# Min_Sys.net
KiCad netlist of a schematic drawn in Altium Designer
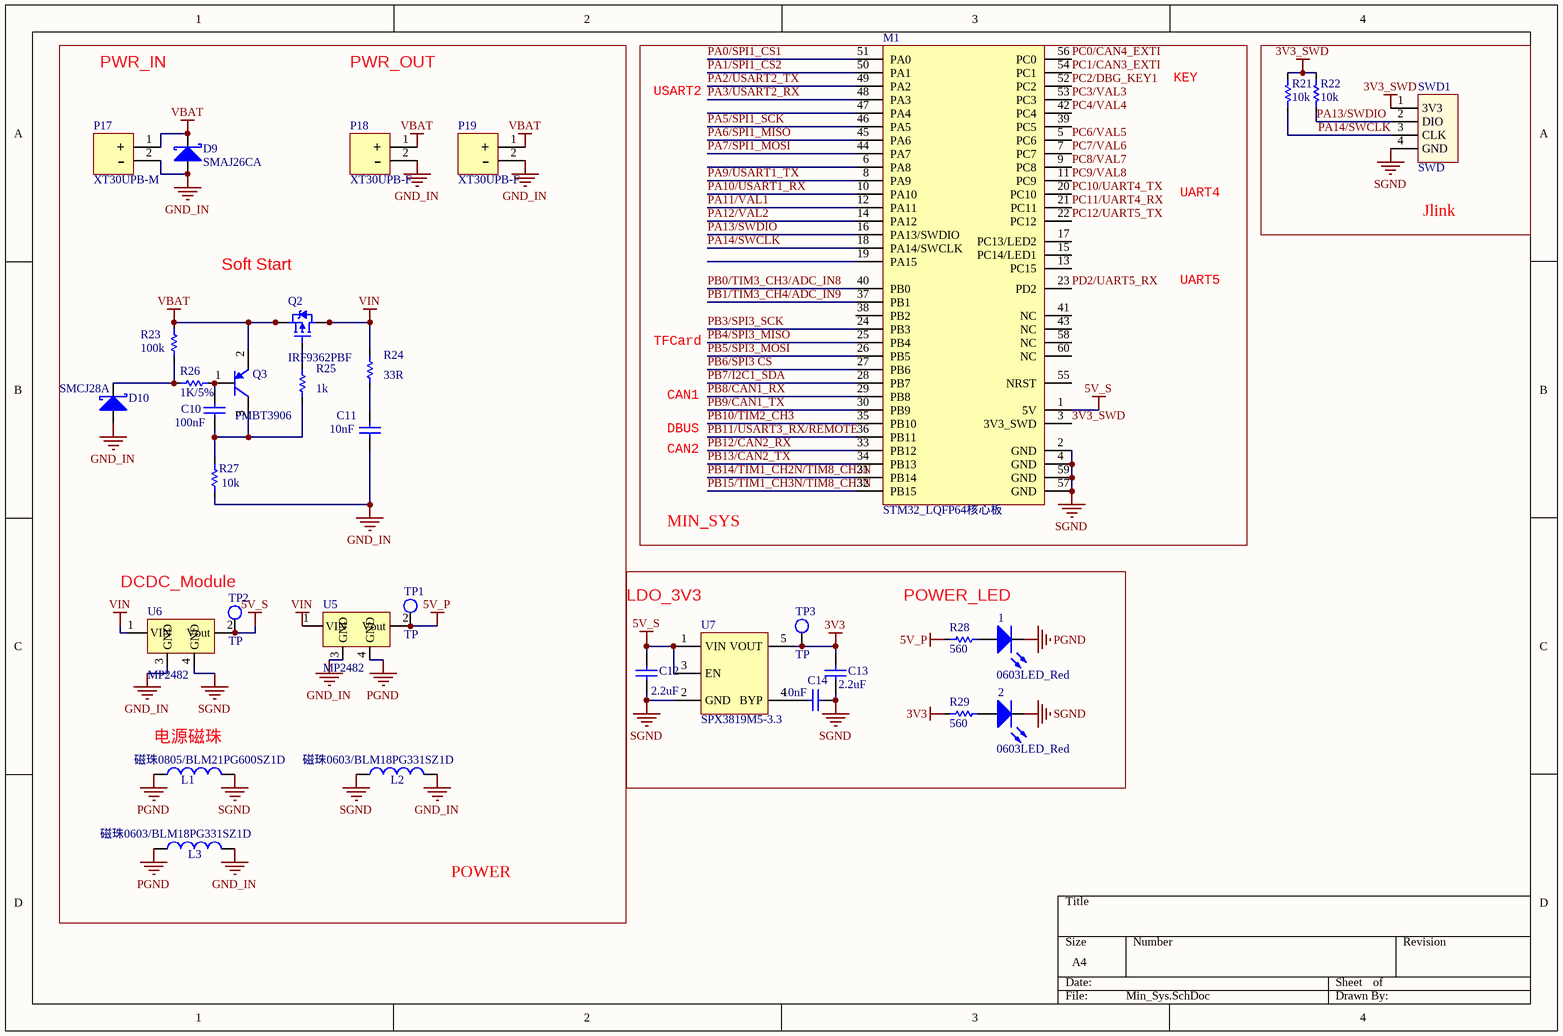
[diagram p0: Min_Sys.SchDoc]

(export (version "E")
  (design (tool "Eeschema 10.0.6"))
  (components
    (comp (ref "1")
      (value "0603LED_Red")
      (footprint "0603LED_R")
      (description "Typical RED, GREEN, YELLOW, AMBER GaAs LED")
      (fields (field (name "PUBLISHER") "Altium Limited"))
      (libsource (lib "MyComponents_v2.5") (part "LED"))
    )
    (comp (ref "2")
      (value "0603LED_Red")
      (footprint "0603LED_R")
      (description "Typical RED, GREEN, YELLOW, AMBER GaAs LED")
      (fields (field (name "PUBLISHER") "Altium Limited"))
      (libsource (lib "MyComponents_v2.5") (part "LED"))
    )
    (comp (ref "C10")
      (value "100nF")
      (footprint "0603C")
      (description "Capacitor")
      (fields (field (name "PUBLISHER") "Altium Limited"))
      (libsource (lib "") (part "Cap_1"))
    )
    (comp (ref "C11")
      (value "10nF")
      (footprint "0603C")
      (description "Capacitor")
      (fields (field (name "PUBLISHER") "Altium Limited"))
      (libsource (lib "") (part "Cap_1"))
    )
    (comp (ref "C12")
      (value "2.2uF")
      (footprint "0603C")
      (description "Capacitor")
      (fields (field (name "PUBLISHER") "Altium Limited"))
      (libsource (lib "MyComponents_v2.5") (part "Cap"))
    )
    (comp (ref "C13")
      (value "2.2uF")
      (footprint "0603C")
      (description "Capacitor")
      (fields (field (name "PUBLISHER") "Altium Limited"))
      (libsource (lib "MyComponents_v2.5") (part "Cap"))
    )
    (comp (ref "C14")
      (value "10nF")
      (footprint "0603C")
      (description "Capacitor")
      (fields (field (name "PUBLISHER") "Altium Limited"))
      (libsource (lib "MyComponents_v2.5") (part "Cap"))
    )
    (comp (ref "D9")
      (value "SMAJ26CA")
      (footprint "SMA/DO-214AC")
      (description "Schottky Diode")
      (fields (field (name "PUBLISHER") "Altium Limited"))
      (libsource (lib "MyComponents_v2.5") (part "D Schottky_SMAF"))
    )
    (comp (ref "D10")
      (value "SMCJ28A")
      (footprint "SMA/DO-214AC")
      (description "Schottky Diode")
      (fields (field (name "PUBLISHER") "Altium Limited"))
      (libsource (lib "MyComponents_v2.5") (part "D Schottky_SMAF"))
    )
    (comp (ref "L1")
      (value "磁珠0805/BLM21PG600SZ1D")
      (footprint "0805L")
      (description "Inductor")
      (fields (field (name "PUBLISHER") "Altium Limited"))
      (libsource (lib "MyComponents_v2.5") (part "Inductor"))
    )
    (comp (ref "L2")
      (value "磁珠0603/BLM18PG331SZ1D")
      (footprint "0603L")
      (description "Inductor")
      (fields (field (name "PUBLISHER") "Altium Limited"))
      (libsource (lib "MyComponents_v2.5") (part "Inductor"))
    )
    (comp (ref "L3")
      (value "磁珠0603/BLM18PG331SZ1D")
      (footprint "0603L")
      (description "Inductor")
      (fields (field (name "PUBLISHER") "Altium Limited"))
      (libsource (lib "MyComponents_v2.5") (part "Inductor"))
    )
    (comp (ref "M1")
      (value "STM32_LQFP64核心板")
      (footprint "STM32_LQFP64核心板")
      (description "STM32_LQFP64核心板\r\n兼容F105Rx、F405RGT6、F446Rx\r\n尺寸23mm x 25mm")
      (libsource (lib "MyComponents_v2.5") (part "STM32_LQFP64核心板"))
    )
    (comp (ref "P17")
      (value "XT30UPB-M")
      (footprint "XT30UPB-MALE")
      (libsource (lib "MyComponents_v2.5") (part "XT30/60/90"))
    )
    (comp (ref "P18")
      (value "XT30UPB-F")
      (footprint "XT30UPB-FEMALE")
      (libsource (lib "MyComponents_v2.5") (part "XT30/60/90"))
    )
    (comp (ref "P19")
      (value "XT30UPB-F")
      (footprint "XT30UPB-FEMALE")
      (libsource (lib "MyComponents_v2.5") (part "XT30/60/90"))
    )
    (comp (ref "Q2")
      (value "IRF9362PBF")
      (footprint "SON5X6")
      (description "P-Channel Power MOSFET")
      (fields (field (name "PUBLISHER") "Altium Limited"))
      (libsource (lib "MyComponents_v2.5") (part "PMOS"))
    )
    (comp (ref "Q3")
      (value "PMBT3906")
      (footprint "SOT-23-3")
      (description "PNP Bipolar Transistor")
      (fields (field (name "PUBLISHER") "Altium Limited"))
      (libsource (lib "MyComponents_v2.5") (part "PNP"))
    )
    (comp (ref "R21")
      (value "10k")
      (footprint "0603R")
      (description "Resistor")
      (fields (field (name "PUBLISHER") "Altium Limited"))
      (libsource (lib "") (part "Res1_1"))
    )
    (comp (ref "R22")
      (value "10k")
      (footprint "0603R")
      (description "Resistor")
      (fields (field (name "PUBLISHER") "Altium Limited"))
      (libsource (lib "") (part "Res1_1"))
    )
    (comp (ref "R23")
      (value "100k")
      (footprint "0603R")
      (description "Resistor")
      (fields (field (name "PUBLISHER") "Altium Limited"))
      (libsource (lib "MyComponents_v2.5") (part "Res1"))
    )
    (comp (ref "R24")
      (value "33R")
      (footprint "0603R")
      (description "Resistor")
      (fields (field (name "PUBLISHER") "Altium Limited"))
      (libsource (lib "MyComponents_v2.5") (part "Res1"))
    )
    (comp (ref "R25")
      (value "1k")
      (footprint "0603R")
      (description "Resistor")
      (fields (field (name "PUBLISHER") "Altium Limited"))
      (libsource (lib "MyComponents_v2.5") (part "Res1"))
    )
    (comp (ref "R26")
      (value "1K/5%")
      (footprint "0603R")
      (description "Resistor")
      (fields (field (name "PUBLISHER") "Altium Limited"))
      (libsource (lib "MyComponents_v2.5") (part "Res1"))
    )
    (comp (ref "R27")
      (value "10k")
      (footprint "0603R")
      (description "Resistor")
      (fields (field (name "PUBLISHER") "Altium Limited"))
      (libsource (lib "MyComponents_v2.5") (part "Res1"))
    )
    (comp (ref "R28")
      (value "560")
      (footprint "0603R")
      (description "Resistor")
      (fields (field (name "PUBLISHER") "Altium Limited"))
      (libsource (lib "") (part "Res1_1"))
    )
    (comp (ref "R29")
      (value "560")
      (footprint "0603R")
      (description "Resistor")
      (fields (field (name "PUBLISHER") "Altium Limited"))
      (libsource (lib "") (part "Res1_1"))
    )
    (comp (ref "SWD1")
      (value "SWD")
      (footprint "HEADER 4x1")
      (libsource (lib "MyComponents_v2.5") (part "SWD_HEADER"))
    )
    (comp (ref "TP1")
      (value "TP")
      (footprint "TP_VIA")
      (description "Test Point")
      (libsource (lib "MyComponents_v2.5") (part "TP"))
    )
    (comp (ref "TP2")
      (value "TP")
      (footprint "TP_VIA")
      (description "Test Point")
      (libsource (lib "MyComponents_v2.5") (part "TP"))
    )
    (comp (ref "TP3")
      (value "TP")
      (footprint "TP_VIA")
      (description "Test Point")
      (libsource (lib "MyComponents_v2.5") (part "TP"))
    )
    (comp (ref "U5")
      (value "MP2482")
      (footprint "MP2482_PowerModule")
      (libsource (lib "MyComponents_v2.5") (part "MP2482_PowerModule"))
    )
    (comp (ref "U6")
      (value "MP2482")
      (footprint "MP2482_PowerModule")
      (libsource (lib "MyComponents_v2.5") (part "MP2482_PowerModule"))
    )
    (comp (ref "U7")
      (value "SPX3819M5-3.3")
      (footprint "SOT-23-5 L")
      (libsource (lib "MyComponents_v2.5") (part "LDO_SOT23-5"))
    )
  )
  (nets
    (net (code "1") (name "/PA0{slash}SPI1_CS1") (class "Default")
      (node (ref "M1") (pin "51") (pinfunction "PA0_51") (pintype "passive"))
    )
    (net (code "2") (name "/PA1{slash}SPI1_CS2") (class "Default")
      (node (ref "M1") (pin "50") (pinfunction "PA1_50") (pintype "passive"))
    )
    (net (code "3") (name "/PA2{slash}USART2_TX") (class "Default")
      (node (ref "M1") (pin "49") (pinfunction "PA2_49") (pintype "passive"))
    )
    (net (code "4") (name "/PA3{slash}USART2_RX") (class "Default")
      (node (ref "M1") (pin "48") (pinfunction "PA3_48") (pintype "passive"))
    )
    (net (code "5") (name "/PA5{slash}SPI1_SCK") (class "Default")
      (node (ref "M1") (pin "46") (pinfunction "PA5_46") (pintype "passive"))
    )
    (net (code "6") (name "/PA6{slash}SPI1_MISO") (class "Default")
      (node (ref "M1") (pin "45") (pinfunction "PA6_45") (pintype "passive"))
    )
    (net (code "7") (name "/PA7{slash}SPI1_MOSI") (class "Default")
      (node (ref "M1") (pin "44") (pinfunction "PA7_44") (pintype "passive"))
    )
    (net (code "8") (name "/PA9{slash}USART1_TX") (class "Default")
      (node (ref "M1") (pin "8") (pinfunction "PA9_8") (pintype "passive"))
    )
    (net (code "9") (name "/PA10{slash}USART1_RX") (class "Default")
      (node (ref "M1") (pin "10") (pinfunction "PA10_10") (pintype "passive"))
    )
    (net (code "10") (name "/PA11{slash}VAL1") (class "Default")
      (node (ref "M1") (pin "12") (pinfunction "PA11_12") (pintype "passive"))
    )
    (net (code "11") (name "/PA12{slash}VAL2") (class "Default")
      (node (ref "M1") (pin "14") (pinfunction "PA12_14") (pintype "passive"))
    )
    (net (code "12") (name "/PA13{slash}SWDIO") (class "Default")
      (node (ref "M1") (pin "16") (pinfunction "PA13/SWDIO_16") (pintype "passive"))
      (node (ref "R22") (pin "1") (pinfunction "1_1") (pintype "passive"))
      (node (ref "SWD1") (pin "2") (pinfunction "DIO_2") (pintype "passive"))
    )
    (net (code "13") (name "/PA14{slash}SWCLK") (class "Default")
      (node (ref "M1") (pin "18") (pinfunction "PA14/SWCLK_18") (pintype "passive"))
      (node (ref "R21") (pin "1") (pinfunction "1_1") (pintype "passive"))
      (node (ref "SWD1") (pin "3") (pinfunction "CLK_3") (pintype "passive"))
    )
    (net (code "14") (name "/PB0{slash}TIM3_CH3{slash}ADC_IN8") (class "Default")
      (node (ref "M1") (pin "40") (pinfunction "PB0_40") (pintype "passive"))
    )
    (net (code "15") (name "/PB1{slash}TIM3_CH4{slash}ADC_IN9") (class "Default")
      (node (ref "M1") (pin "37") (pinfunction "PB1_37") (pintype "passive"))
    )
    (net (code "16") (name "/PB3{slash}SPI3_SCK") (class "Default")
      (node (ref "M1") (pin "24") (pinfunction "PB3_24") (pintype "passive"))
    )
    (net (code "17") (name "/PB4{slash}SPI3_MISO") (class "Default")
      (node (ref "M1") (pin "25") (pinfunction "PB4_25") (pintype "passive"))
    )
    (net (code "18") (name "/PB5{slash}SPI3_MOSI") (class "Default")
      (node (ref "M1") (pin "26") (pinfunction "PB5_26") (pintype "passive"))
    )
    (net (code "19") (name "/PB6{slash}SPI3 CS") (class "Default")
      (node (ref "M1") (pin "27") (pinfunction "PB6_27") (pintype "passive"))
    )
    (net (code "20") (name "/PB7{slash}I2C1_SDA") (class "Default")
      (node (ref "M1") (pin "28") (pinfunction "PB7_28") (pintype "passive"))
    )
    (net (code "21") (name "/PB8{slash}CAN1_RX") (class "Default")
      (node (ref "M1") (pin "29") (pinfunction "PB8_29") (pintype "passive"))
    )
    (net (code "22") (name "/PB9{slash}CAN1_TX") (class "Default")
      (node (ref "M1") (pin "30") (pinfunction "PB9_30") (pintype "passive"))
    )
    (net (code "23") (name "/PB10{slash}TIM2_CH3") (class "Default")
      (node (ref "M1") (pin "35") (pinfunction "PB10_35") (pintype "passive"))
    )
    (net (code "24") (name "/PB11{slash}USART3_RX{slash}REMOTE") (class "Default")
      (node (ref "M1") (pin "36") (pinfunction "PB11_36") (pintype "passive"))
    )
    (net (code "25") (name "/PB12{slash}CAN2_RX") (class "Default")
      (node (ref "M1") (pin "33") (pinfunction "PB12_33") (pintype "passive"))
    )
    (net (code "26") (name "/PB13{slash}CAN2_TX") (class "Default")
      (node (ref "M1") (pin "34") (pinfunction "PB13_34") (pintype "passive"))
    )
    (net (code "27") (name "/PB14{slash}TIM1_CH2N{slash}TIM8_CH2N") (class "Default")
      (node (ref "M1") (pin "31") (pinfunction "PB14_31") (pintype "passive"))
    )
    (net (code "28") (name "/PB15{slash}TIM1_CH3N{slash}TIM8_CH3N") (class "Default")
      (node (ref "M1") (pin "32") (pinfunction "PB15_32") (pintype "passive"))
    )
    (net (code "29") (name "/PC0{slash}CAN4_EXTI") (class "Default")
      (node (ref "M1") (pin "56") (pinfunction "PC0_56") (pintype "passive"))
    )
    (net (code "30") (name "/PC1{slash}CAN3_EXTI") (class "Default")
      (node (ref "M1") (pin "54") (pinfunction "PC1_54") (pintype "passive"))
    )
    (net (code "31") (name "/PC2{slash}DBG_KEY1") (class "Default")
      (node (ref "M1") (pin "52") (pinfunction "PC2_52") (pintype "passive"))
    )
    (net (code "32") (name "/PC3{slash}VAL3") (class "Default")
      (node (ref "M1") (pin "53") (pinfunction "PC3_53") (pintype "passive"))
    )
    (net (code "33") (name "/PC4{slash}VAL4") (class "Default")
      (node (ref "M1") (pin "42") (pinfunction "PC4_42") (pintype "passive"))
    )
    (net (code "34") (name "/PC6{slash}VAL5") (class "Default")
      (node (ref "M1") (pin "5") (pinfunction "PC6_5") (pintype "passive"))
    )
    (net (code "35") (name "/PC7{slash}VAL6") (class "Default")
      (node (ref "M1") (pin "7") (pinfunction "PC7_7") (pintype "passive"))
    )
    (net (code "36") (name "/PC8{slash}VAL7") (class "Default")
      (node (ref "M1") (pin "9") (pinfunction "PC8_9") (pintype "passive"))
    )
    (net (code "37") (name "/PC9{slash}VAL8") (class "Default")
      (node (ref "M1") (pin "11") (pinfunction "PC9_11") (pintype "passive"))
    )
    (net (code "38") (name "/PC10{slash}UART4_TX") (class "Default")
      (node (ref "M1") (pin "20") (pinfunction "PC10_20") (pintype "passive"))
    )
    (net (code "39") (name "/PC11{slash}UART4_RX") (class "Default")
      (node (ref "M1") (pin "21") (pinfunction "PC11_21") (pintype "passive"))
    )
    (net (code "40") (name "/PC12{slash}UART5_TX") (class "Default")
      (node (ref "M1") (pin "22") (pinfunction "PC12_22") (pintype "passive"))
    )
    (net (code "41") (name "/PD2{slash}UART5_RX") (class "Default")
      (node (ref "M1") (pin "23") (pinfunction "PD2_23") (pintype "passive"))
    )
    (net (code "42") (name "3V3") (class "Default")
      (node (ref "C13") (pin "1") (pinfunction "1_1") (pintype "passive"))
      (node (ref "R29") (pin "2") (pinfunction "2_2") (pintype "passive"))
      (node (ref "TP3") (pin "1") (pinfunction "TP_1") (pintype "open_collector"))
      (node (ref "U7") (pin "5") (pinfunction "VOUT_5") (pintype "passive"))
    )
    (net (code "43") (name "3V3_SWD") (class "Default")
      (node (ref "M1") (pin "3") (pinfunction "3V3_SWD_3") (pintype "passive"))
      (node (ref "R21") (pin "2") (pinfunction "2_2") (pintype "passive"))
      (node (ref "R22") (pin "2") (pinfunction "2_2") (pintype "passive"))
      (node (ref "SWD1") (pin "1") (pinfunction "3V3_1") (pintype "passive"))
    )
    (net (code "44") (name "5V_P") (class "Default")
      (node (ref "R28") (pin "2") (pinfunction "2_2") (pintype "passive"))
      (node (ref "TP1") (pin "1") (pinfunction "TP_1") (pintype "open_collector"))
      (node (ref "U5") (pin "2") (pinfunction "Vout_2") (pintype "passive"))
    )
    (net (code "45") (name "5V_S") (class "Default")
      (node (ref "C12") (pin "2") (pinfunction "2_2") (pintype "passive"))
      (node (ref "M1") (pin "1") (pinfunction "5V_1") (pintype "passive"))
      (node (ref "TP2") (pin "1") (pinfunction "TP_1") (pintype "open_collector"))
      (node (ref "U6") (pin "2") (pinfunction "Vout_2") (pintype "passive"))
      (node (ref "U7") (pin "1") (pinfunction "VIN_1") (pintype "passive"))
      (node (ref "U7") (pin "3") (pinfunction "EN_3") (pintype "passive"))
    )
    (net (code "46") (name "GND_IN") (class "Default")
      (node (ref "C11") (pin "1") (pinfunction "1_1") (pintype "passive"))
      (node (ref "D10") (pin "1") (pinfunction "1_1") (pintype "passive"))
      (node (ref "D9") (pin "1") (pinfunction "1_1") (pintype "passive"))
      (node (ref "L2") (pin "2") (pinfunction "2_2") (pintype "passive"))
      (node (ref "L3") (pin "2") (pinfunction "2_2") (pintype "passive"))
      (node (ref "P17") (pin "2") (pinfunction "-_2") (pintype "passive"))
      (node (ref "P18") (pin "2") (pinfunction "-_2") (pintype "passive"))
      (node (ref "P19") (pin "2") (pinfunction "-_2") (pintype "passive"))
      (node (ref "R27") (pin "2") (pinfunction "2_2") (pintype "passive"))
      (node (ref "U5") (pin "3") (pinfunction "GND_3") (pintype "passive"))
      (node (ref "U6") (pin "3") (pinfunction "GND_3") (pintype "passive"))
    )
    (net (code "47") (name "Net-(1-Pad1)") (class "Default")
      (node (ref "1") (pin "1") (pinfunction "1_1") (pintype "passive"))
      (node (ref "R28") (pin "1") (pinfunction "1_1") (pintype "passive"))
    )
    (net (code "48") (name "Net-(2-Pad1)") (class "Default")
      (node (ref "2") (pin "1") (pinfunction "1_1") (pintype "passive"))
      (node (ref "R29") (pin "1") (pinfunction "1_1") (pintype "passive"))
    )
    (net (code "49") (name "Net-(C11-Pad2)") (class "Default")
      (node (ref "C11") (pin "2") (pinfunction "2_2") (pintype "passive"))
      (node (ref "R24") (pin "2") (pinfunction "2_2") (pintype "passive"))
    )
    (net (code "50") (name "Net-(D10-Pad2)") (class "Default")
      (node (ref "D10") (pin "2") (pinfunction "2_2") (pintype "passive"))
      (node (ref "R23") (pin "2") (pinfunction "2_2") (pintype "passive"))
      (node (ref "R26") (pin "1") (pinfunction "1_1") (pintype "passive"))
    )
    (net (code "51") (name "Net-(Q2-G)") (class "Default")
      (node (ref "Q2") (pin "4") (pinfunction "G_4") (pintype "passive"))
      (node (ref "R25") (pin "1") (pinfunction "1_1") (pintype "passive"))
    )
    (net (code "52") (name "Net-(Q3-B)") (class "Default")
      (node (ref "C10") (pin "2") (pinfunction "2_2") (pintype "passive"))
      (node (ref "Q3") (pin "1") (pinfunction "B_1") (pintype "passive"))
      (node (ref "R26") (pin "2") (pinfunction "2_2") (pintype "passive"))
    )
    (net (code "53") (name "Net-(Q3-C)") (class "Default")
      (node (ref "C10") (pin "1") (pinfunction "1_1") (pintype "passive"))
      (node (ref "Q3") (pin "3") (pinfunction "C_3") (pintype "passive"))
      (node (ref "R25") (pin "2") (pinfunction "2_2") (pintype "passive"))
      (node (ref "R27") (pin "1") (pinfunction "1_1") (pintype "passive"))
    )
    (net (code "54") (name "Net-(U7-BYP)") (class "Default")
      (node (ref "C14") (pin "2") (pinfunction "2_2") (pintype "passive"))
      (node (ref "U7") (pin "4") (pinfunction "BYP_4") (pintype "passive"))
    )
    (net (code "55") (name "PGND") (class "Default")
      (node (ref "1") (pin "2") (pinfunction "2_2") (pintype "passive"))
      (node (ref "L1") (pin "1") (pinfunction "1_1") (pintype "passive"))
      (node (ref "L3") (pin "1") (pinfunction "1_1") (pintype "passive"))
      (node (ref "U5") (pin "4") (pinfunction "GND_4") (pintype "passive"))
    )
    (net (code "56") (name "SGND") (class "Default")
      (node (ref "2") (pin "2") (pinfunction "2_2") (pintype "passive"))
      (node (ref "C12") (pin "1") (pinfunction "1_1") (pintype "passive"))
      (node (ref "C13") (pin "2") (pinfunction "2_2") (pintype "passive"))
      (node (ref "C14") (pin "1") (pinfunction "1_1") (pintype "passive"))
      (node (ref "L1") (pin "2") (pinfunction "2_2") (pintype "passive"))
      (node (ref "L2") (pin "1") (pinfunction "1_1") (pintype "passive"))
      (node (ref "M1") (pin "2") (pinfunction "GND_2") (pintype "passive"))
      (node (ref "M1") (pin "4") (pinfunction "GND_4") (pintype "passive"))
      (node (ref "M1") (pin "57") (pinfunction "GND_57") (pintype "passive"))
      (node (ref "M1") (pin "59") (pinfunction "GND_59") (pintype "passive"))
      (node (ref "SWD1") (pin "4") (pinfunction "GND_4") (pintype "passive"))
      (node (ref "U6") (pin "4") (pinfunction "GND_4") (pintype "passive"))
      (node (ref "U7") (pin "2") (pinfunction "GND_2") (pintype "passive"))
    )
    (net (code "57") (name "VBAT") (class "Default")
      (node (ref "D9") (pin "2") (pinfunction "2_2") (pintype "passive"))
      (node (ref "P17") (pin "1") (pinfunction "+_1") (pintype "passive"))
      (node (ref "P18") (pin "1") (pinfunction "+_1") (pintype "passive"))
      (node (ref "P19") (pin "1") (pinfunction "+_1") (pintype "passive"))
      (node (ref "Q2") (pin "1") (pinfunction "S_1") (pintype "passive"))
      (node (ref "Q2") (pin "2") (pinfunction "S_2") (pintype "passive"))
      (node (ref "Q2") (pin "3") (pinfunction "S_3") (pintype "passive"))
      (node (ref "Q3") (pin "2") (pinfunction "E_2") (pintype "passive"))
      (node (ref "R23") (pin "1") (pinfunction "1_1") (pintype "passive"))
    )
    (net (code "58") (name "VIN") (class "Default")
      (node (ref "Q2") (pin "5") (pinfunction "D_5") (pintype "passive"))
      (node (ref "Q2") (pin "6") (pinfunction "D_6") (pintype "passive"))
      (node (ref "Q2") (pin "7") (pinfunction "D_7") (pintype "passive"))
      (node (ref "Q2") (pin "8") (pinfunction "D_8") (pintype "passive"))
      (node (ref "Q2") (pin "9") (pinfunction "D_9") (pintype "passive"))
      (node (ref "R24") (pin "1") (pinfunction "1_1") (pintype "passive"))
      (node (ref "U5") (pin "1") (pinfunction "VIN_1") (pintype "passive"))
      (node (ref "U6") (pin "1") (pinfunction "VIN_1") (pintype "passive"))
    )
    (net (code "59") (name "unconnected-(M1-NC-Pad41)") (class "Default")
      (node (ref "M1") (pin "41") (pinfunction "NC_41") (pintype "passive"))
    )
    (net (code "60") (name "unconnected-(M1-NC-Pad43)") (class "Default")
      (node (ref "M1") (pin "43") (pinfunction "NC_43") (pintype "passive"))
    )
    (net (code "61") (name "unconnected-(M1-NC-Pad58)") (class "Default")
      (node (ref "M1") (pin "58") (pinfunction "NC_58") (pintype "passive"))
    )
    (net (code "62") (name "unconnected-(M1-NC-Pad60)") (class "Default")
      (node (ref "M1") (pin "60") (pinfunction "NC_60") (pintype "passive"))
    )
    (net (code "63") (name "unconnected-(M1-NRST-Pad55)") (class "Default")
      (node (ref "M1") (pin "55") (pinfunction "NRST_55") (pintype "passive"))
    )
    (net (code "64") (name "unconnected-(M1-PA4-Pad47)") (class "Default")
      (node (ref "M1") (pin "47") (pinfunction "PA4_47") (pintype "passive"))
    )
    (net (code "65") (name "unconnected-(M1-PA8-Pad6)") (class "Default")
      (node (ref "M1") (pin "6") (pinfunction "PA8_6") (pintype "passive"))
    )
    (net (code "66") (name "unconnected-(M1-PA15-Pad19)") (class "Default")
      (node (ref "M1") (pin "19") (pinfunction "PA15_19") (pintype "passive"))
    )
    (net (code "67") (name "unconnected-(M1-PB2-Pad38)") (class "Default")
      (node (ref "M1") (pin "38") (pinfunction "PB2_38") (pintype "passive"))
    )
    (net (code "68") (name "unconnected-(M1-PC5-Pad39)") (class "Default")
      (node (ref "M1") (pin "39") (pinfunction "PC5_39") (pintype "passive"))
    )
    (net (code "69") (name "unconnected-(M1-PC13{slash}LED2-Pad17)") (class "Default")
      (node (ref "M1") (pin "17") (pinfunction "PC13/LED2_17") (pintype "passive"))
    )
    (net (code "70") (name "unconnected-(M1-PC14{slash}LED1-Pad15)") (class "Default")
      (node (ref "M1") (pin "15") (pinfunction "PC14/LED1_15") (pintype "passive"))
    )
    (net (code "71") (name "unconnected-(M1-PC15-Pad13)") (class "Default")
      (node (ref "M1") (pin "13") (pinfunction "PC15_13") (pintype "passive"))
    )
  )
)
